# CurrentMetter.net
KiCad netlist of a schematic drawn in EAGLE
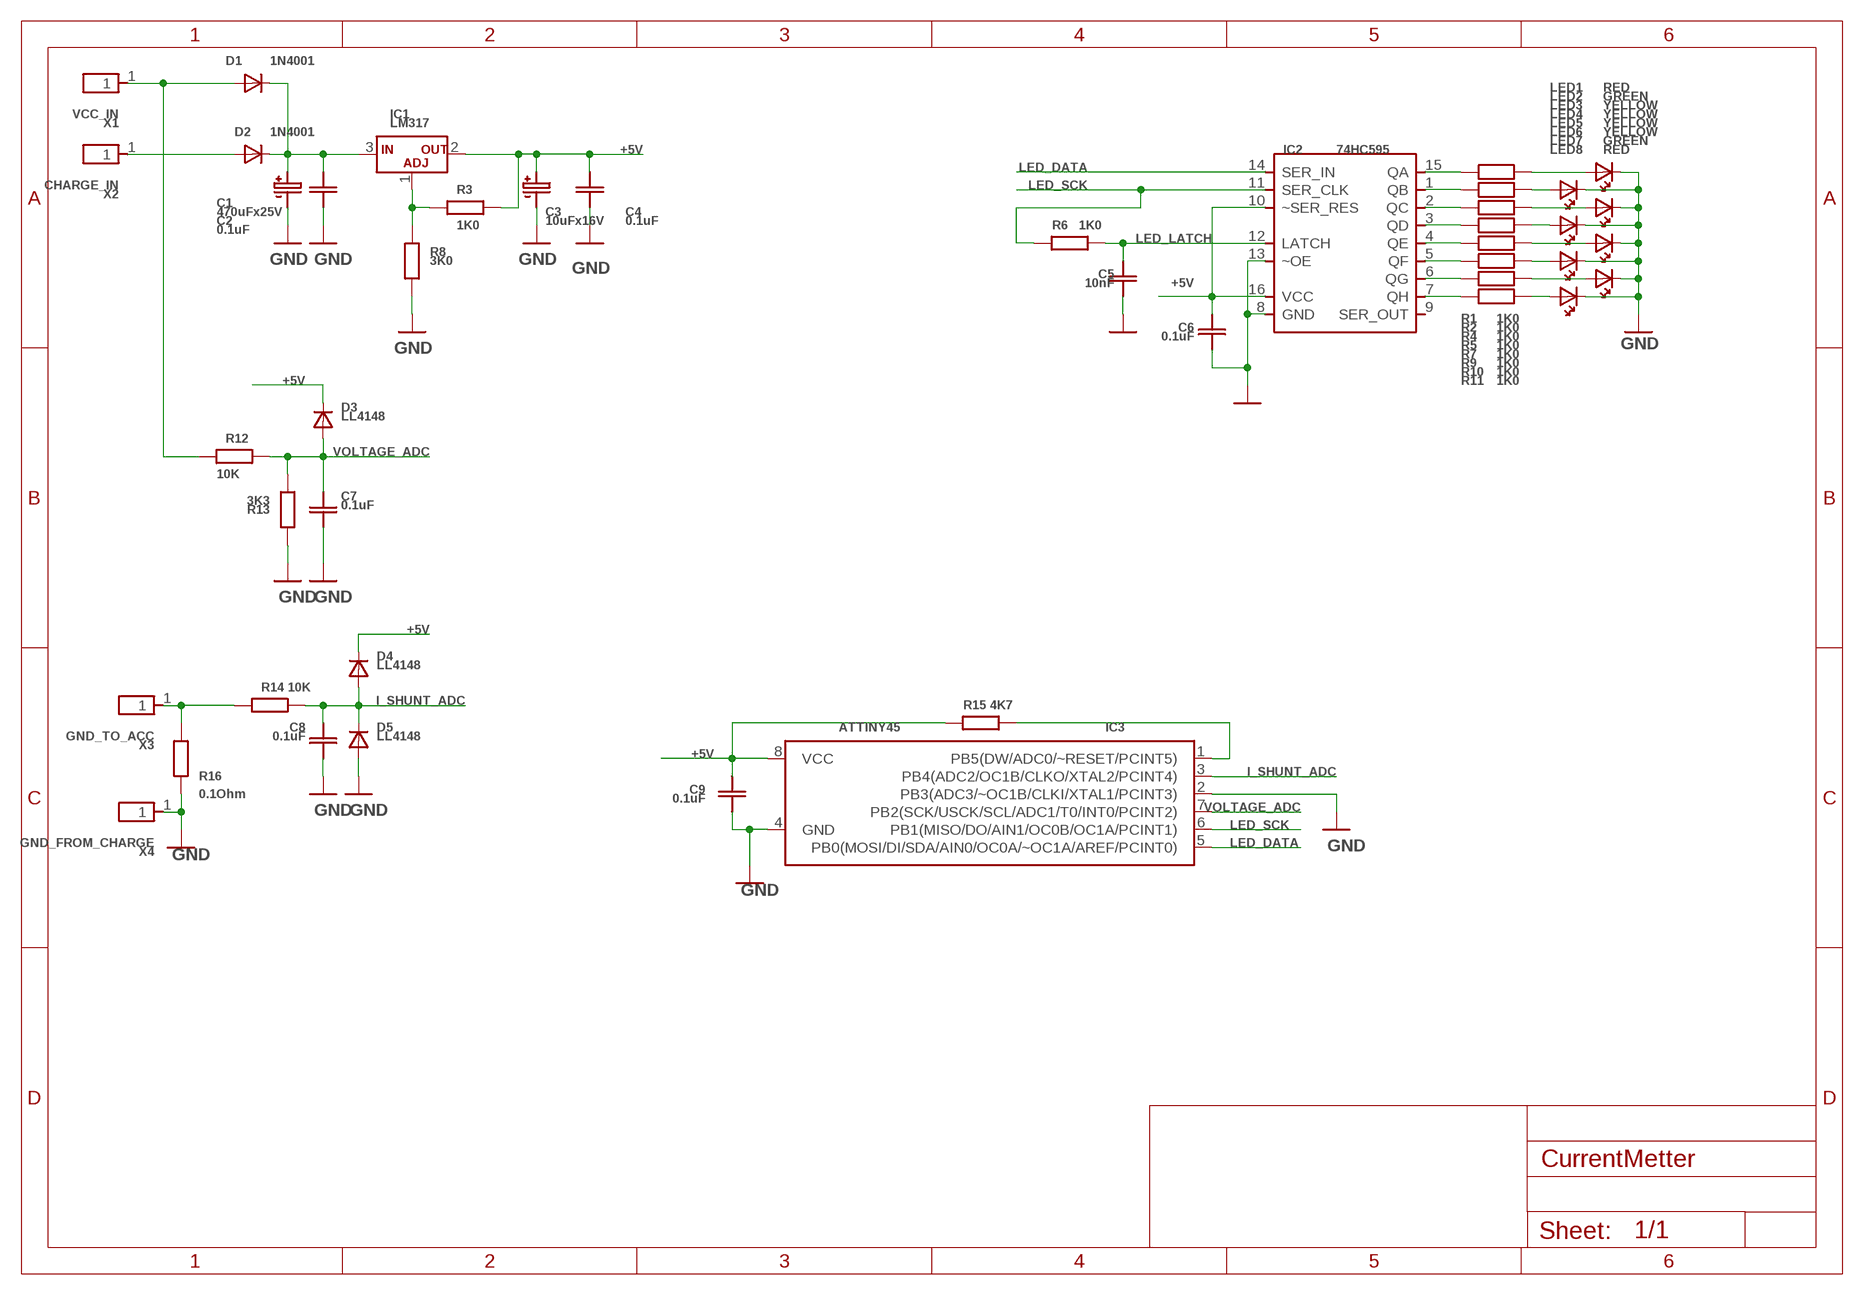
[diagram p0: schematic, sheet 1]

(export (version "E")
  (design (tool "Eeschema 10.0.6"))
  (components
    (comp (ref "C1")
      (value "470uFx25V")
      (footprint "eagle-import:CE_6.3MM")
      (libsource (lib "eagle-import") (part "CE6.3MM"))
    )
    (comp (ref "C2")
      (value "0.1uF")
      (footprint "eagle-import:RSMD_0805")
      (libsource (lib "eagle-import") (part "CSMD_0805"))
    )
    (comp (ref "C3")
      (value "10uFx16V")
      (footprint "eagle-import:CE_5.2MM")
      (libsource (lib "eagle-import") (part "CE5.2MM"))
    )
    (comp (ref "C4")
      (value "0.1uF")
      (footprint "eagle-import:RSMD_0805")
      (libsource (lib "eagle-import") (part "CSMD_0805"))
    )
    (comp (ref "C5")
      (value "10nF")
      (footprint "eagle-import:RSMD_0805")
      (libsource (lib "eagle-import") (part "CSMD_0805"))
    )
    (comp (ref "C6")
      (value "0.1uF")
      (footprint "eagle-import:RSMD_0805")
      (libsource (lib "eagle-import") (part "CSMD_0805"))
    )
    (comp (ref "C7")
      (value "0.1uF")
      (footprint "eagle-import:RSMD_0805")
      (libsource (lib "eagle-import") (part "CSMD_0805"))
    )
    (comp (ref "C8")
      (value "0.1uF")
      (footprint "eagle-import:RSMD_0805")
      (libsource (lib "eagle-import") (part "CSMD_0805"))
    )
    (comp (ref "C9")
      (value "0.1uF")
      (footprint "eagle-import:RSMD_0805")
      (libsource (lib "eagle-import") (part "CSMD_0805"))
    )
    (comp (ref "D1")
      (value "1N4001")
      (footprint "eagle-import:DO-41_10MM")
      (libsource (lib "eagle-import") (part "1N4001DO-41_10MM"))
    )
    (comp (ref "D2")
      (value "1N4001")
      (footprint "eagle-import:DO-41_10MM")
      (libsource (lib "eagle-import") (part "1N4001DO-41_10MM"))
    )
    (comp (ref "D3")
      (value "LL4148")
      (footprint "eagle-import:SOD-80")
      (libsource (lib "eagle-import") (part "LL4147SOD-80"))
    )
    (comp (ref "D4")
      (value "LL4148")
      (footprint "eagle-import:SOD-80")
      (libsource (lib "eagle-import") (part "LL4147SOD-80"))
    )
    (comp (ref "D5")
      (value "LL4148")
      (footprint "eagle-import:SOD-80")
      (libsource (lib "eagle-import") (part "LL4147SOD-80"))
    )
    (comp (ref "IC1")
      (value "LM317")
      (footprint "eagle-import:D2PAK")
      (libsource (lib "eagle-import") (part "LM317(D2PAK)"))
    )
    (comp (ref "IC2")
      (value "74HC595")
      (footprint "eagle-import:SOIC16")
      (libsource (lib "eagle-import") (part "74HC595(SOIC16)"))
    )
    (comp (ref "IC3")
      (value "ATTINY45")
      (footprint "eagle-import:SOIC8(0.15'')")
      (libsource (lib "eagle-import") (part "ATTINY45(SOIC8-0.15'')"))
    )
    (comp (ref "LED1")
      (value "RED")
      (footprint "eagle-import:LED3MM")
      (libsource (lib "eagle-import") (part "LED3MM"))
    )
    (comp (ref "LED2")
      (value "GREEN")
      (footprint "eagle-import:LED3MM")
      (libsource (lib "eagle-import") (part "LED3MM"))
    )
    (comp (ref "LED3")
      (value "YELLOW")
      (footprint "eagle-import:LED3MM")
      (libsource (lib "eagle-import") (part "LED3MM"))
    )
    (comp (ref "LED4")
      (value "YELLOW")
      (footprint "eagle-import:LED3MM")
      (libsource (lib "eagle-import") (part "LED3MM"))
    )
    (comp (ref "LED5")
      (value "YELLOW")
      (footprint "eagle-import:LED3MM")
      (libsource (lib "eagle-import") (part "LED3MM"))
    )
    (comp (ref "LED6")
      (value "YELLOW")
      (footprint "eagle-import:LED3MM")
      (libsource (lib "eagle-import") (part "LED3MM"))
    )
    (comp (ref "LED7")
      (value "GREEN")
      (footprint "eagle-import:LED3MM")
      (libsource (lib "eagle-import") (part "LED3MM"))
    )
    (comp (ref "LED8")
      (value "RED")
      (footprint "eagle-import:LED3MM")
      (libsource (lib "eagle-import") (part "LED3MM"))
    )
    (comp (ref "R1")
      (value "1K0")
      (footprint "eagle-import:RSMD_1206")
      (libsource (lib "eagle-import") (part "RSMD_1206"))
    )
    (comp (ref "R2")
      (value "1K0")
      (footprint "eagle-import:RSMD_0805")
      (libsource (lib "eagle-import") (part "RSMD_0805"))
    )
    (comp (ref "R3")
      (value "1K0")
      (footprint "eagle-import:RSMD_0805")
      (libsource (lib "eagle-import") (part "RSMD_0805"))
    )
    (comp (ref "R4")
      (value "1K0")
      (footprint "eagle-import:RSMD_0805")
      (libsource (lib "eagle-import") (part "RSMD_0805"))
    )
    (comp (ref "R5")
      (value "1K0")
      (footprint "eagle-import:RSMD_0805")
      (libsource (lib "eagle-import") (part "RSMD_0805"))
    )
    (comp (ref "R6")
      (value "1K0")
      (footprint "eagle-import:RSMD_0805")
      (libsource (lib "eagle-import") (part "RSMD_0805"))
    )
    (comp (ref "R7")
      (value "1K0")
      (footprint "eagle-import:RSMD_0805")
      (libsource (lib "eagle-import") (part "RSMD_0805"))
    )
    (comp (ref "R8")
      (value "3K0")
      (footprint "eagle-import:RSMD_0805")
      (libsource (lib "eagle-import") (part "RSMD_0805"))
    )
    (comp (ref "R9")
      (value "1K0")
      (footprint "eagle-import:RSMD_0805")
      (libsource (lib "eagle-import") (part "RSMD_0805"))
    )
    (comp (ref "R10")
      (value "1K0")
      (footprint "eagle-import:RSMD_0805")
      (libsource (lib "eagle-import") (part "RSMD_0805"))
    )
    (comp (ref "R11")
      (value "1K0")
      (footprint "eagle-import:RSMD_0805")
      (libsource (lib "eagle-import") (part "RSMD_0805"))
    )
    (comp (ref "R12")
      (value "10K")
      (footprint "eagle-import:RSMD_1206_BIG_GAP")
      (libsource (lib "eagle-import") (part "RSMD_1206_BIG_GAP"))
    )
    (comp (ref "R13")
      (value "3K3")
      (footprint "eagle-import:RSMD_0805")
      (libsource (lib "eagle-import") (part "RSMD_0805"))
    )
    (comp (ref "R14")
      (value "10K")
      (footprint "eagle-import:RSMD_0805")
      (libsource (lib "eagle-import") (part "RSMD_0805"))
    )
    (comp (ref "R15")
      (value "4K7")
      (footprint "eagle-import:RSMD_0805")
      (libsource (lib "eagle-import") (part "RSMD_0805"))
    )
    (comp (ref "R16")
      (value "0.1Ohm")
      (footprint "eagle-import:R_1.0W")
      (libsource (lib "eagle-import") (part "R1.0W"))
    )
    (comp (ref "X1")
      (value "VCC_IN")
      (footprint "eagle-import:PIN1X1_3.5MM_SIDE_BOARD")
      (libsource (lib "eagle-import") (part "PIN1X13.5MM_SIDE_BOARD"))
    )
    (comp (ref "X2")
      (value "CHARGE_IN")
      (footprint "eagle-import:PIN1X1_3.5MM_SIDE_BOARD")
      (libsource (lib "eagle-import") (part "PIN1X13.5MM_SIDE_BOARD"))
    )
    (comp (ref "X3")
      (value "GND_TO_ACC")
      (footprint "eagle-import:PIN1X1_3.5MM_SIDE_BOARD")
      (libsource (lib "eagle-import") (part "PIN1X13.5MM_SIDE_BOARD"))
    )
    (comp (ref "X4")
      (value "GND_FROM_CHARGE")
      (footprint "eagle-import:PIN1X1_3.5MM_SIDE_BOARD")
      (libsource (lib "eagle-import") (part "PIN1X13.5MM_SIDE_BOARD"))
    )
  )
  (nets
    (net (code "1") (name "/+5V") (class "Default")
      (node (ref "C3") (pin "PLUS") (pinfunction "PLUS_PLUS") (pintype "bidirectional"))
      (node (ref "C4") (pin "PAD_0") (pinfunction "PIN0_PAD_0") (pintype "bidirectional"))
      (node (ref "C6") (pin "PAD_0") (pinfunction "PIN0_PAD_0") (pintype "bidirectional"))
      (node (ref "C9") (pin "PAD_0") (pinfunction "PIN0_PAD_0") (pintype "bidirectional"))
      (node (ref "D3") (pin "CATHODE") (pinfunction "CATHODE_CATHODE") (pintype "passive"))
      (node (ref "D4") (pin "CATHODE") (pinfunction "CATHODE_CATHODE") (pintype "passive"))
      (node (ref "IC1") (pin "2") (pinfunction "OUT_2") (pintype "output"))
      (node (ref "IC2") (pin "10") (pinfunction "~{SER_RES}_10") (pintype "bidirectional"))
      (node (ref "IC2") (pin "16") (pinfunction "VCC_16") (pintype "bidirectional"))
      (node (ref "IC3") (pin "8") (pinfunction "VCC_8") (pintype "bidirectional"))
      (node (ref "R15") (pin "PAD_0") (pinfunction "PIN0_PAD_0") (pintype "passive"))
      (node (ref "R3") (pin "PAD_1") (pinfunction "PIN1_PAD_1") (pintype "passive"))
    )
    (net (code "2") (name "/I_SHUNT_ADC") (class "Default")
      (node (ref "C8") (pin "PAD_0") (pinfunction "PIN0_PAD_0") (pintype "bidirectional"))
      (node (ref "D4") (pin "ANODE") (pinfunction "ANODE_ANODE") (pintype "passive"))
      (node (ref "D5") (pin "CATHODE") (pinfunction "CATHODE_CATHODE") (pintype "passive"))
      (node (ref "IC3") (pin "3") (pinfunction "PB4(ADC2/OC1B/CLKO/XTAL2/PCINT4)_3") (pintype "bidirectional"))
      (node (ref "R14") (pin "PAD_1") (pinfunction "PIN1_PAD_1") (pintype "passive"))
    )
    (net (code "3") (name "/LED_DATA") (class "Default")
      (node (ref "IC2") (pin "14") (pinfunction "SER_IN_14") (pintype "bidirectional"))
      (node (ref "IC3") (pin "5") (pinfunction "PB0(MOSI/DI/SDA/AIN0/OC0A/~{OC1A/AREF/PCINT0})_5") (pintype "bidirectional"))
    )
    (net (code "4") (name "/LED_LATCH") (class "Default")
      (node (ref "C5") (pin "PAD_0") (pinfunction "PIN0_PAD_0") (pintype "bidirectional"))
      (node (ref "IC2") (pin "12") (pinfunction "LATCH_12") (pintype "bidirectional"))
      (node (ref "R6") (pin "PAD_1") (pinfunction "PIN1_PAD_1") (pintype "passive"))
    )
    (net (code "5") (name "/LED_SCK") (class "Default")
      (node (ref "IC2") (pin "11") (pinfunction "SER_CLK_11") (pintype "bidirectional"))
      (node (ref "IC3") (pin "6") (pinfunction "PB1(MISO/DO/AIN1/OC0B/OC1A/PCINT1)_6") (pintype "bidirectional"))
      (node (ref "R6") (pin "PAD_0") (pinfunction "PIN0_PAD_0") (pintype "passive"))
    )
    (net (code "6") (name "/VOLTAGE_ADC") (class "Default")
      (node (ref "C7") (pin "PAD_0") (pinfunction "PIN0_PAD_0") (pintype "bidirectional"))
      (node (ref "D3") (pin "ANODE") (pinfunction "ANODE_ANODE") (pintype "passive"))
      (node (ref "IC3") (pin "7") (pinfunction "PB2(SCK/USCK/SCL/ADC1/T0/INT0/PCINT2)_7") (pintype "bidirectional"))
      (node (ref "R12") (pin "PAD_1") (pinfunction "PIN1_PAD_1") (pintype "passive"))
      (node (ref "R13") (pin "PAD_1") (pinfunction "PIN1_PAD_1") (pintype "passive"))
    )
    (net (code "7") (name "GND") (class "Default")
      (node (ref "C1") (pin "MINUS") (pinfunction "MINUS_MINUS") (pintype "bidirectional"))
      (node (ref "C2") (pin "PAD_1") (pinfunction "PIN1_PAD_1") (pintype "bidirectional"))
      (node (ref "C3") (pin "MINUS") (pinfunction "MINUS_MINUS") (pintype "bidirectional"))
      (node (ref "C4") (pin "PAD_1") (pinfunction "PIN1_PAD_1") (pintype "bidirectional"))
      (node (ref "C5") (pin "PAD_1") (pinfunction "PIN1_PAD_1") (pintype "bidirectional"))
      (node (ref "C6") (pin "PAD_1") (pinfunction "PIN1_PAD_1") (pintype "bidirectional"))
      (node (ref "C7") (pin "PAD_1") (pinfunction "PIN1_PAD_1") (pintype "bidirectional"))
      (node (ref "C8") (pin "PAD_1") (pinfunction "PIN1_PAD_1") (pintype "bidirectional"))
      (node (ref "C9") (pin "PAD_1") (pinfunction "PIN1_PAD_1") (pintype "bidirectional"))
      (node (ref "D5") (pin "ANODE") (pinfunction "ANODE_ANODE") (pintype "passive"))
      (node (ref "IC2") (pin "13") (pinfunction "~{OE}_13") (pintype "bidirectional"))
      (node (ref "IC2") (pin "8") (pinfunction "GND_8") (pintype "bidirectional"))
      (node (ref "IC3") (pin "2") (pinfunction "PB3(ADC3/~{OC1B/CLKI/XTAL1/PCINT3})_2") (pintype "bidirectional"))
      (node (ref "IC3") (pin "4") (pinfunction "GND_4") (pintype "bidirectional"))
      (node (ref "LED1") (pin "CATHODE") (pinfunction "CATHODE_CATHODE") (pintype "passive"))
      (node (ref "LED2") (pin "CATHODE") (pinfunction "CATHODE_CATHODE") (pintype "passive"))
      (node (ref "LED3") (pin "CATHODE") (pinfunction "CATHODE_CATHODE") (pintype "passive"))
      (node (ref "LED4") (pin "CATHODE") (pinfunction "CATHODE_CATHODE") (pintype "passive"))
      (node (ref "LED5") (pin "CATHODE") (pinfunction "CATHODE_CATHODE") (pintype "passive"))
      (node (ref "LED6") (pin "CATHODE") (pinfunction "CATHODE_CATHODE") (pintype "passive"))
      (node (ref "LED7") (pin "CATHODE") (pinfunction "CATHODE_CATHODE") (pintype "passive"))
      (node (ref "LED8") (pin "CATHODE") (pinfunction "CATHODE_CATHODE") (pintype "passive"))
      (node (ref "R13") (pin "PAD_0") (pinfunction "PIN0_PAD_0") (pintype "passive"))
      (node (ref "R16") (pin "PAD1") (pinfunction "PIN1_PAD1") (pintype "passive"))
      (node (ref "R8") (pin "PAD_0") (pinfunction "PIN0_PAD_0") (pintype "passive"))
      (node (ref "X4") (pin "1") (pinfunction "1_1") (pintype "bidirectional"))
    )
    (net (code "8") (name "Net-(C2-PIN0)") (class "Default")
      (node (ref "C1") (pin "PLUS") (pinfunction "PLUS_PLUS") (pintype "bidirectional"))
      (node (ref "C2") (pin "PAD_0") (pinfunction "PIN0_PAD_0") (pintype "bidirectional"))
      (node (ref "D1") (pin "CATHODE") (pinfunction "CATHODE_CATHODE") (pintype "passive"))
      (node (ref "D2") (pin "CATHODE") (pinfunction "CATHODE_CATHODE") (pintype "passive"))
      (node (ref "IC1") (pin "3") (pinfunction "IN_3") (pintype "input"))
    )
    (net (code "9") (name "Net-(D2-PadANODE)") (class "Default")
      (node (ref "D2") (pin "ANODE") (pinfunction "ANODE_ANODE") (pintype "passive"))
      (node (ref "X2") (pin "1") (pinfunction "1_1") (pintype "bidirectional"))
    )
    (net (code "10") (name "Net-(IC1-ADJ)") (class "Default")
      (node (ref "IC1") (pin "1") (pinfunction "ADJ_1") (pintype "input"))
      (node (ref "R3") (pin "PAD_0") (pinfunction "PIN0_PAD_0") (pintype "passive"))
      (node (ref "R8") (pin "PAD_1") (pinfunction "PIN1_PAD_1") (pintype "passive"))
    )
    (net (code "11") (name "Net-(IC2-QA)") (class "Default")
      (node (ref "IC2") (pin "15") (pinfunction "QA_15") (pintype "bidirectional"))
      (node (ref "R1") (pin "PAD_0") (pinfunction "PIN0_PAD_0") (pintype "passive"))
    )
    (net (code "12") (name "Net-(IC2-QB)") (class "Default")
      (node (ref "IC2") (pin "1") (pinfunction "QB_1") (pintype "bidirectional"))
      (node (ref "R2") (pin "PAD_0") (pinfunction "PIN0_PAD_0") (pintype "passive"))
    )
    (net (code "13") (name "Net-(IC2-QC)") (class "Default")
      (node (ref "IC2") (pin "2") (pinfunction "QC_2") (pintype "bidirectional"))
      (node (ref "R4") (pin "PAD_0") (pinfunction "PIN0_PAD_0") (pintype "passive"))
    )
    (net (code "14") (name "Net-(IC2-QD)") (class "Default")
      (node (ref "IC2") (pin "3") (pinfunction "QD_3") (pintype "bidirectional"))
      (node (ref "R5") (pin "PAD_0") (pinfunction "PIN0_PAD_0") (pintype "passive"))
    )
    (net (code "15") (name "Net-(IC2-QE)") (class "Default")
      (node (ref "IC2") (pin "4") (pinfunction "QE_4") (pintype "bidirectional"))
      (node (ref "R7") (pin "PAD_0") (pinfunction "PIN0_PAD_0") (pintype "passive"))
    )
    (net (code "16") (name "Net-(IC2-QF)") (class "Default")
      (node (ref "IC2") (pin "5") (pinfunction "QF_5") (pintype "bidirectional"))
      (node (ref "R9") (pin "PAD_0") (pinfunction "PIN0_PAD_0") (pintype "passive"))
    )
    (net (code "17") (name "Net-(IC2-QG)") (class "Default")
      (node (ref "IC2") (pin "6") (pinfunction "QG_6") (pintype "bidirectional"))
      (node (ref "R10") (pin "PAD_0") (pinfunction "PIN0_PAD_0") (pintype "passive"))
    )
    (net (code "18") (name "Net-(IC2-QH)") (class "Default")
      (node (ref "IC2") (pin "7") (pinfunction "QH_7") (pintype "bidirectional"))
      (node (ref "R11") (pin "PAD_0") (pinfunction "PIN0_PAD_0") (pintype "passive"))
    )
    (net (code "19") (name "Net-(IC3-PB5(DW{slash}ADC0{slash}~{RESET{slash}PCINT5}))") (class "Default")
      (node (ref "IC3") (pin "1") (pinfunction "PB5(DW/ADC0/~{RESET/PCINT5})_1") (pintype "bidirectional"))
      (node (ref "R15") (pin "PAD_1") (pinfunction "PIN1_PAD_1") (pintype "passive"))
    )
    (net (code "20") (name "Net-(R1-PIN1)") (class "Default")
      (node (ref "LED1") (pin "ANODE") (pinfunction "ANODE_ANODE") (pintype "passive"))
      (node (ref "R1") (pin "PAD_1") (pinfunction "PIN1_PAD_1") (pintype "passive"))
    )
    (net (code "21") (name "Net-(R2-PIN1)") (class "Default")
      (node (ref "LED2") (pin "ANODE") (pinfunction "ANODE_ANODE") (pintype "passive"))
      (node (ref "R2") (pin "PAD_1") (pinfunction "PIN1_PAD_1") (pintype "passive"))
    )
    (net (code "22") (name "Net-(R4-PIN1)") (class "Default")
      (node (ref "LED3") (pin "ANODE") (pinfunction "ANODE_ANODE") (pintype "passive"))
      (node (ref "R4") (pin "PAD_1") (pinfunction "PIN1_PAD_1") (pintype "passive"))
    )
    (net (code "23") (name "Net-(R5-PIN1)") (class "Default")
      (node (ref "LED4") (pin "ANODE") (pinfunction "ANODE_ANODE") (pintype "passive"))
      (node (ref "R5") (pin "PAD_1") (pinfunction "PIN1_PAD_1") (pintype "passive"))
    )
    (net (code "24") (name "Net-(R7-PIN1)") (class "Default")
      (node (ref "LED5") (pin "ANODE") (pinfunction "ANODE_ANODE") (pintype "passive"))
      (node (ref "R7") (pin "PAD_1") (pinfunction "PIN1_PAD_1") (pintype "passive"))
    )
    (net (code "25") (name "Net-(R9-PIN1)") (class "Default")
      (node (ref "LED6") (pin "ANODE") (pinfunction "ANODE_ANODE") (pintype "passive"))
      (node (ref "R9") (pin "PAD_1") (pinfunction "PIN1_PAD_1") (pintype "passive"))
    )
    (net (code "26") (name "Net-(R10-PIN1)") (class "Default")
      (node (ref "LED7") (pin "ANODE") (pinfunction "ANODE_ANODE") (pintype "passive"))
      (node (ref "R10") (pin "PAD_1") (pinfunction "PIN1_PAD_1") (pintype "passive"))
    )
    (net (code "27") (name "Net-(R11-PIN1)") (class "Default")
      (node (ref "LED8") (pin "ANODE") (pinfunction "ANODE_ANODE") (pintype "passive"))
      (node (ref "R11") (pin "PAD_1") (pinfunction "PIN1_PAD_1") (pintype "passive"))
    )
    (net (code "28") (name "Net-(R12-PIN0)") (class "Default")
      (node (ref "D1") (pin "ANODE") (pinfunction "ANODE_ANODE") (pintype "passive"))
      (node (ref "R12") (pin "PAD_0") (pinfunction "PIN0_PAD_0") (pintype "passive"))
      (node (ref "X1") (pin "1") (pinfunction "1_1") (pintype "bidirectional"))
    )
    (net (code "29") (name "Net-(R14-PIN0)") (class "Default")
      (node (ref "R14") (pin "PAD_0") (pinfunction "PIN0_PAD_0") (pintype "passive"))
      (node (ref "R16") (pin "PAD_0") (pinfunction "PIN0_PAD_0") (pintype "passive"))
      (node (ref "X3") (pin "1") (pinfunction "1_1") (pintype "bidirectional"))
    )
    (net (code "30") (name "unconnected-(IC2-SER_OUT-Pad9)") (class "Default")
      (node (ref "IC2") (pin "9") (pinfunction "SER_OUT_9") (pintype "bidirectional"))
    )
  )
)
